# SCH_miniArcade.net
KiCad netlist of a schematic drawn in EasyEDA
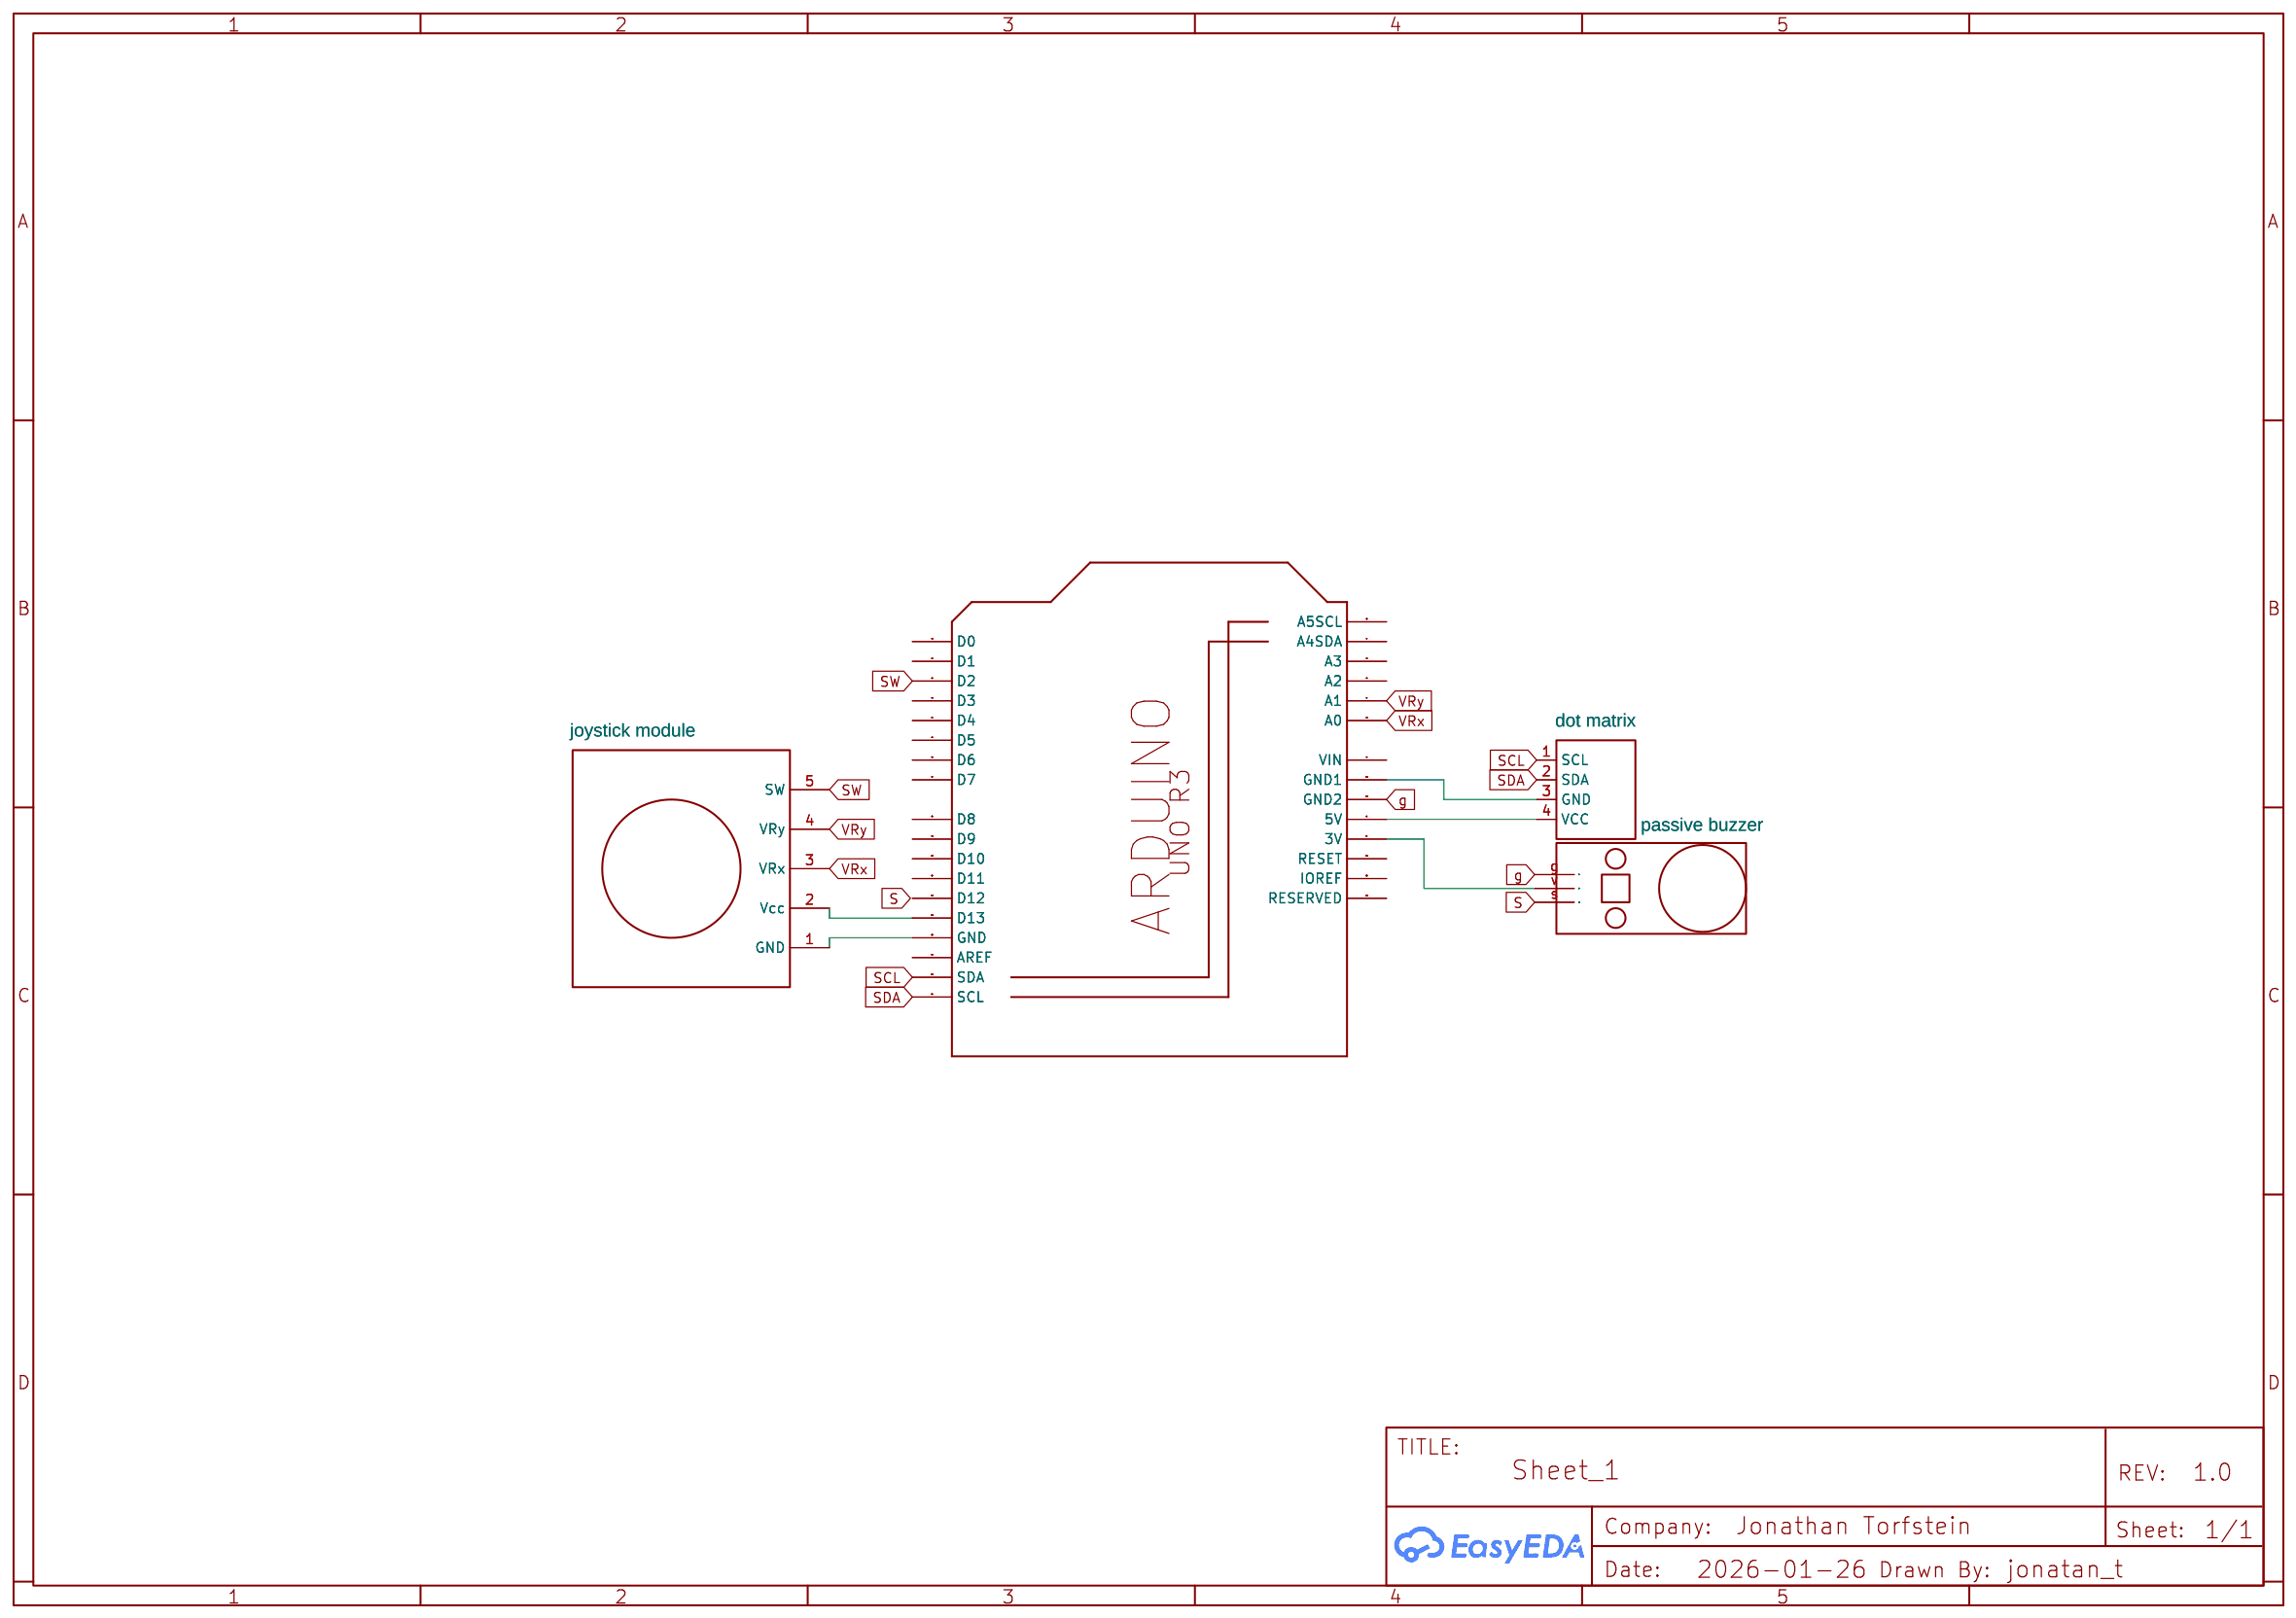
[diagram p0: schematic sheet]

(export (version "E")
  (design (tool "Eeschema 10.0.6"))
  (components
    (comp (ref "U1") (value "ARDUINOR3-DIMENSION") (libsource (lib "") (part "ARDUINOR3-DIMENSION")))
    (comp (ref "U2")
      (value "dot matrix")
      (fields
        (field (name "Manufacturer Part") "350424-1")
        (field (name "Manufacturer") "TE Connectivity(泰科电子)")
      )
      (libsource (lib "") (part "350424-1"))
    )
    (comp (ref "U3") (value "joystick module") (libsource (lib "") (part "HW-504JOYSTICK")))
    (comp (ref "U4") (value "passive buzzer") (libsource (lib "") (part "keystudio passive buzzer")))
  )
  (nets
    (net (code "1") (name "Net-(U2-GND)") (class "Default")
      (node (ref "U1") (pin "GND1") (pinfunction "GND1_GND1") (pintype "passive"))
      (node (ref "U2") (pin "3") (pinfunction "GND_3") (pintype "unspecified"))
    )
    (net (code "2") (name "Net-(U2-VCC)") (class "Default")
      (node (ref "U1") (pin "5V") (pinfunction "5V_5V") (pintype "passive"))
      (node (ref "U2") (pin "4") (pinfunction "VCC_4") (pintype "unspecified"))
    )
    (net (code "3") (name "Net-(U3-GND)") (class "Default")
      (node (ref "U1") (pin "GND") (pinfunction "GND_GND") (pintype "passive"))
      (node (ref "U3") (pin "1") (pinfunction "GND_1") (pintype "unspecified"))
    )
    (net (code "4") (name "Net-(U3-Vcc)") (class "Default")
      (node (ref "U1") (pin "D13") (pinfunction "D13_D13") (pintype "unspecified"))
      (node (ref "U3") (pin "2") (pinfunction "Vcc_2") (pintype "unspecified"))
    )
    (net (code "5") (name "Net-(U4-2)") (class "Default")
      (node (ref "U1") (pin "3V") (pinfunction "3V_3V") (pintype "passive"))
      (node (ref "U4") (pin "v") (pinfunction "2_v") (pintype "unspecified"))
    )
    (net (code "6") (name "S") (class "Default")
      (node (ref "U4") (pin "s") (pinfunction "3_s") (pintype "unspecified"))
    )
    (net (code "7") (name "SCL") (class "Default")
      (node (ref "U1") (pin "SDA") (pinfunction "SDA_SDA") (pintype "unspecified"))
      (node (ref "U2") (pin "1") (pinfunction "SCL_1") (pintype "unspecified"))
    )
    (net (code "8") (name "SDA") (class "Default")
      (node (ref "U1") (pin "SCL") (pinfunction "SCL_SCL") (pintype "unspecified"))
      (node (ref "U2") (pin "2") (pinfunction "SDA_2") (pintype "unspecified"))
    )
    (net (code "9") (name "SW") (class "Default")
      (node (ref "U1") (pin "D2") (pinfunction "D2_D2") (pintype "unspecified"))
      (node (ref "U3") (pin "5") (pinfunction "SW_5") (pintype "unspecified"))
    )
    (net (code "10") (name "VRx") (class "Default")
      (node (ref "U1") (pin "A0") (pinfunction "A0_A0") (pintype "unspecified"))
      (node (ref "U3") (pin "3") (pinfunction "VRx_3") (pintype "unspecified"))
    )
    (net (code "11") (name "VRy") (class "Default")
      (node (ref "U1") (pin "A1") (pinfunction "A1_A1") (pintype "unspecified"))
      (node (ref "U3") (pin "4") (pinfunction "VRy_4") (pintype "unspecified"))
    )
    (net (code "12") (name "g") (class "Default")
      (node (ref "U1") (pin "GND2") (pinfunction "GND2_GND2") (pintype "passive"))
      (node (ref "U4") (pin "g") (pinfunction "1_g") (pintype "unspecified"))
    )
    (net (code "13") (name "unconnected-(U1-A4SDA-PadA4)") (class "Default")
      (node (ref "U1") (pin "A4") (pinfunction "A4SDA_A4") (pintype "unspecified"))
    )
    (net (code "14") (name "unconnected-(U1-A5SCL-PadA5)") (class "Default")
      (node (ref "U1") (pin "A5") (pinfunction "A5SCL_A5") (pintype "unspecified"))
    )
    (net (code "15") (name "unconnected-(U1-PadA2)") (class "Default")
      (node (ref "U1") (pin "A2") (pinfunction "A2_A2") (pintype "unspecified"))
    )
    (net (code "16") (name "unconnected-(U1-PadA3)") (class "Default")
      (node (ref "U1") (pin "A3") (pinfunction "A3_A3") (pintype "unspecified"))
    )
    (net (code "17") (name "unconnected-(U1-PadAREF)") (class "Default")
      (node (ref "U1") (pin "AREF") (pinfunction "AREF_AREF") (pintype "unspecified"))
    )
    (net (code "18") (name "unconnected-(U1-PadD0)") (class "Default")
      (node (ref "U1") (pin "D0") (pinfunction "D0_D0") (pintype "unspecified"))
    )
    (net (code "19") (name "unconnected-(U1-PadD1)") (class "Default")
      (node (ref "U1") (pin "D1") (pinfunction "D1_D1") (pintype "unspecified"))
    )
    (net (code "20") (name "unconnected-(U1-PadD3)") (class "Default")
      (node (ref "U1") (pin "D3") (pinfunction "D3_D3") (pintype "unspecified"))
    )
    (net (code "21") (name "unconnected-(U1-PadD4)") (class "Default")
      (node (ref "U1") (pin "D4") (pinfunction "D4_D4") (pintype "unspecified"))
    )
    (net (code "22") (name "unconnected-(U1-PadD5)") (class "Default")
      (node (ref "U1") (pin "D5") (pinfunction "D5_D5") (pintype "unspecified"))
    )
    (net (code "23") (name "unconnected-(U1-PadD6)") (class "Default")
      (node (ref "U1") (pin "D6") (pinfunction "D6_D6") (pintype "unspecified"))
    )
    (net (code "24") (name "unconnected-(U1-PadD7)") (class "Default")
      (node (ref "U1") (pin "D7") (pinfunction "D7_D7") (pintype "unspecified"))
    )
    (net (code "25") (name "unconnected-(U1-PadD8)") (class "Default")
      (node (ref "U1") (pin "D8") (pinfunction "D8_D8") (pintype "unspecified"))
    )
    (net (code "26") (name "unconnected-(U1-PadD9)") (class "Default")
      (node (ref "U1") (pin "D9") (pinfunction "D9_D9") (pintype "unspecified"))
    )
    (net (code "27") (name "unconnected-(U1-PadD10)") (class "Default")
      (node (ref "U1") (pin "D10") (pinfunction "D10_D10") (pintype "unspecified"))
    )
    (net (code "28") (name "unconnected-(U1-PadD11)") (class "Default")
      (node (ref "U1") (pin "D11") (pinfunction "D11_D11") (pintype "unspecified"))
    )
    (net (code "29") (name "unconnected-(U1-PadD12)") (class "Default")
      (node (ref "U1") (pin "D12") (pinfunction "D12_D12") (pintype "unspecified"))
    )
    (net (code "30") (name "unconnected-(U1-PadIOREF)") (class "Default")
      (node (ref "U1") (pin "IOREF") (pinfunction "IOREF_IOREF") (pintype "output"))
    )
    (net (code "31") (name "unconnected-(U1-PadRESERVED)") (class "Default")
      (node (ref "U1") (pin "RESERVED") (pinfunction "RESERVED_RESERVED") (pintype "unspecified"))
    )
    (net (code "32") (name "unconnected-(U1-PadRESET)") (class "Default")
      (node (ref "U1") (pin "RESET") (pinfunction "RESET_RESET") (pintype "unspecified"))
    )
    (net (code "33") (name "unconnected-(U1-PadVIN)") (class "Default")
      (node (ref "U1") (pin "VIN") (pinfunction "VIN_VIN") (pintype "passive"))
    )
  )
)
